# KIT_STM32F4.net
KiCad netlist of a schematic drawn in Altium Designer
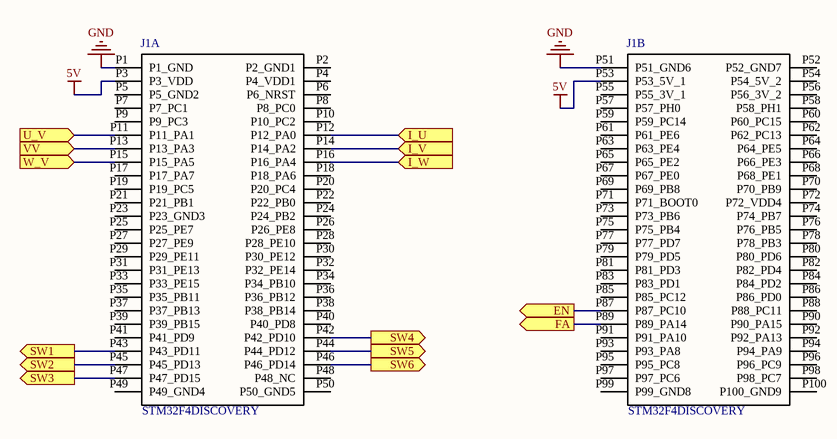
[diagram p0: KIT_STM32F4.SchDoc]

(export (version "E")
  (design (tool "Eeschema 10.0.6"))
  (components
    (comp (ref "J1")
      (value "STM32F4DISCOVERY")
      (footprint "STMICROELECTRONICS_STM32F4DISCOVERY_STM32F4DISCOVERY(Primary)")
      (description "Development kit: ARM ST; pin strips, pin header; No.of")
      (fields (field (name "MF") "STMicroelectronics"))
      (libsource (lib "SemacSYS") (part "STM32F4DISCOVERY"))
    )
  )
  (nets
    (net (code "1") (name "/EN") (class "Default")
      (node (ref "J1") (pin "P87") (pinfunction "P87_PC10_P87") (pintype "passive"))
    )
    (net (code "2") (name "/FA") (class "Default")
      (node (ref "J1") (pin "P89") (pinfunction "P89_PA14_P89") (pintype "passive"))
    )
    (net (code "3") (name "/I_U") (class "Default")
      (node (ref "J1") (pin "P12") (pinfunction "P12_PA0_P12") (pintype "passive"))
    )
    (net (code "4") (name "/I_V") (class "Default")
      (node (ref "J1") (pin "P14") (pinfunction "P14_PA2_P14") (pintype "passive"))
    )
    (net (code "5") (name "/I_W") (class "Default")
      (node (ref "J1") (pin "P16") (pinfunction "P16_PA4_P16") (pintype "passive"))
    )
    (net (code "6") (name "/SW1") (class "Default")
      (node (ref "J1") (pin "P43") (pinfunction "P43_PD11_P43") (pintype "passive"))
    )
    (net (code "7") (name "/SW2") (class "Default")
      (node (ref "J1") (pin "P45") (pinfunction "P45_PD13_P45") (pintype "passive"))
    )
    (net (code "8") (name "/SW3") (class "Default")
      (node (ref "J1") (pin "P47") (pinfunction "P47_PD15_P47") (pintype "passive"))
    )
    (net (code "9") (name "/SW4") (class "Default")
      (node (ref "J1") (pin "P42") (pinfunction "P42_PD10_P42") (pintype "passive"))
    )
    (net (code "10") (name "/SW5") (class "Default")
      (node (ref "J1") (pin "P44") (pinfunction "P44_PD12_P44") (pintype "passive"))
    )
    (net (code "11") (name "/SW6") (class "Default")
      (node (ref "J1") (pin "P46") (pinfunction "P46_PD14_P46") (pintype "passive"))
    )
    (net (code "12") (name "/U_V") (class "Default")
      (node (ref "J1") (pin "P11") (pinfunction "P11_PA1_P11") (pintype "passive"))
    )
    (net (code "13") (name "/VV") (class "Default")
      (node (ref "J1") (pin "P13") (pinfunction "P13_PA3_P13") (pintype "passive"))
    )
    (net (code "14") (name "/W_V") (class "Default")
      (node (ref "J1") (pin "P15") (pinfunction "P15_PA5_P15") (pintype "passive"))
    )
    (net (code "15") (name "5V") (class "Default")
      (node (ref "J1") (pin "P3") (pinfunction "P3_VDD_P3") (pintype "passive"))
      (node (ref "J1") (pin "P53") (pinfunction "P53_5V_1_P53") (pintype "passive"))
    )
    (net (code "16") (name "GND") (class "Default")
      (node (ref "J1") (pin "P1") (pinfunction "P1_GND_P1") (pintype "passive"))
      (node (ref "J1") (pin "P51") (pinfunction "P51_GND6_P51") (pintype "passive"))
    )
    (net (code "17") (name "unconnected-(J1A-P2_GND1-PadP2)") (class "Default")
      (node (ref "J1") (pin "P2") (pinfunction "P2_GND1_P2") (pintype "passive"))
    )
    (net (code "18") (name "unconnected-(J1A-P4_VDD1-PadP4)") (class "Default")
      (node (ref "J1") (pin "P4") (pinfunction "P4_VDD1_P4") (pintype "passive"))
    )
    (net (code "19") (name "unconnected-(J1A-P5_GND2-PadP5)") (class "Default")
      (node (ref "J1") (pin "P5") (pinfunction "P5_GND2_P5") (pintype "passive"))
    )
    (net (code "20") (name "unconnected-(J1A-P6_NRST-PadP6)") (class "Default")
      (node (ref "J1") (pin "P6") (pinfunction "P6_NRST_P6") (pintype "passive"))
    )
    (net (code "21") (name "unconnected-(J1A-P7_PC1-PadP7)") (class "Default")
      (node (ref "J1") (pin "P7") (pinfunction "P7_PC1_P7") (pintype "passive"))
    )
    (net (code "22") (name "unconnected-(J1A-P8_PC0-PadP8)") (class "Default")
      (node (ref "J1") (pin "P8") (pinfunction "P8_PC0_P8") (pintype "passive"))
    )
    (net (code "23") (name "unconnected-(J1A-P9_PC3-PadP9)") (class "Default")
      (node (ref "J1") (pin "P9") (pinfunction "P9_PC3_P9") (pintype "passive"))
    )
    (net (code "24") (name "unconnected-(J1A-P10_PC2-PadP10)") (class "Default")
      (node (ref "J1") (pin "P10") (pinfunction "P10_PC2_P10") (pintype "passive"))
    )
    (net (code "25") (name "unconnected-(J1A-P17_PA7-PadP17)") (class "Default")
      (node (ref "J1") (pin "P17") (pinfunction "P17_PA7_P17") (pintype "passive"))
    )
    (net (code "26") (name "unconnected-(J1A-P18_PA6-PadP18)") (class "Default")
      (node (ref "J1") (pin "P18") (pinfunction "P18_PA6_P18") (pintype "passive"))
    )
    (net (code "27") (name "unconnected-(J1A-P19_PC5-PadP19)") (class "Default")
      (node (ref "J1") (pin "P19") (pinfunction "P19_PC5_P19") (pintype "passive"))
    )
    (net (code "28") (name "unconnected-(J1A-P20_PC4-PadP20)") (class "Default")
      (node (ref "J1") (pin "P20") (pinfunction "P20_PC4_P20") (pintype "passive"))
    )
    (net (code "29") (name "unconnected-(J1A-P21_PB1-PadP21)") (class "Default")
      (node (ref "J1") (pin "P21") (pinfunction "P21_PB1_P21") (pintype "passive"))
    )
    (net (code "30") (name "unconnected-(J1A-P22_PB0-PadP22)") (class "Default")
      (node (ref "J1") (pin "P22") (pinfunction "P22_PB0_P22") (pintype "passive"))
    )
    (net (code "31") (name "unconnected-(J1A-P23_GND3-PadP23)") (class "Default")
      (node (ref "J1") (pin "P23") (pinfunction "P23_GND3_P23") (pintype "passive"))
    )
    (net (code "32") (name "unconnected-(J1A-P24_PB2-PadP24)") (class "Default")
      (node (ref "J1") (pin "P24") (pinfunction "P24_PB2_P24") (pintype "passive"))
    )
    (net (code "33") (name "unconnected-(J1A-P25_PE7-PadP25)") (class "Default")
      (node (ref "J1") (pin "P25") (pinfunction "P25_PE7_P25") (pintype "passive"))
    )
    (net (code "34") (name "unconnected-(J1A-P26_PE8-PadP26)") (class "Default")
      (node (ref "J1") (pin "P26") (pinfunction "P26_PE8_P26") (pintype "passive"))
    )
    (net (code "35") (name "unconnected-(J1A-P27_PE9-PadP27)") (class "Default")
      (node (ref "J1") (pin "P27") (pinfunction "P27_PE9_P27") (pintype "passive"))
    )
    (net (code "36") (name "unconnected-(J1A-P28_PE10-PadP28)") (class "Default")
      (node (ref "J1") (pin "P28") (pinfunction "P28_PE10_P28") (pintype "passive"))
    )
    (net (code "37") (name "unconnected-(J1A-P29_PE11-PadP29)") (class "Default")
      (node (ref "J1") (pin "P29") (pinfunction "P29_PE11_P29") (pintype "passive"))
    )
    (net (code "38") (name "unconnected-(J1A-P30_PE12-PadP30)") (class "Default")
      (node (ref "J1") (pin "P30") (pinfunction "P30_PE12_P30") (pintype "passive"))
    )
    (net (code "39") (name "unconnected-(J1A-P31_PE13-PadP31)") (class "Default")
      (node (ref "J1") (pin "P31") (pinfunction "P31_PE13_P31") (pintype "passive"))
    )
    (net (code "40") (name "unconnected-(J1A-P32_PE14-PadP32)") (class "Default")
      (node (ref "J1") (pin "P32") (pinfunction "P32_PE14_P32") (pintype "passive"))
    )
    (net (code "41") (name "unconnected-(J1A-P33_PE15-PadP33)") (class "Default")
      (node (ref "J1") (pin "P33") (pinfunction "P33_PE15_P33") (pintype "passive"))
    )
    (net (code "42") (name "unconnected-(J1A-P34_PB10-PadP34)") (class "Default")
      (node (ref "J1") (pin "P34") (pinfunction "P34_PB10_P34") (pintype "passive"))
    )
    (net (code "43") (name "unconnected-(J1A-P35_PB11-PadP35)") (class "Default")
      (node (ref "J1") (pin "P35") (pinfunction "P35_PB11_P35") (pintype "passive"))
    )
    (net (code "44") (name "unconnected-(J1A-P36_PB12-PadP36)") (class "Default")
      (node (ref "J1") (pin "P36") (pinfunction "P36_PB12_P36") (pintype "passive"))
    )
    (net (code "45") (name "unconnected-(J1A-P37_PB13-PadP37)") (class "Default")
      (node (ref "J1") (pin "P37") (pinfunction "P37_PB13_P37") (pintype "passive"))
    )
    (net (code "46") (name "unconnected-(J1A-P38_PB14-PadP38)") (class "Default")
      (node (ref "J1") (pin "P38") (pinfunction "P38_PB14_P38") (pintype "passive"))
    )
    (net (code "47") (name "unconnected-(J1A-P39_PB15-PadP39)") (class "Default")
      (node (ref "J1") (pin "P39") (pinfunction "P39_PB15_P39") (pintype "passive"))
    )
    (net (code "48") (name "unconnected-(J1A-P40_PD8-PadP40)") (class "Default")
      (node (ref "J1") (pin "P40") (pinfunction "P40_PD8_P40") (pintype "passive"))
    )
    (net (code "49") (name "unconnected-(J1A-P41_PD9-PadP41)") (class "Default")
      (node (ref "J1") (pin "P41") (pinfunction "P41_PD9_P41") (pintype "passive"))
    )
    (net (code "50") (name "unconnected-(J1A-P48_NC-PadP48)") (class "Default")
      (node (ref "J1") (pin "P48") (pinfunction "P48_NC_P48") (pintype "passive"))
    )
    (net (code "51") (name "unconnected-(J1A-P49_GND4-PadP49)") (class "Default")
      (node (ref "J1") (pin "P49") (pinfunction "P49_GND4_P49") (pintype "passive"))
    )
    (net (code "52") (name "unconnected-(J1A-P50_GND5-PadP50)") (class "Default")
      (node (ref "J1") (pin "P50") (pinfunction "P50_GND5_P50") (pintype "passive"))
    )
    (net (code "53") (name "unconnected-(J1B-P52_GND7-PadP52)") (class "Default")
      (node (ref "J1") (pin "P52") (pinfunction "P52_GND7_P52") (pintype "passive"))
    )
    (net (code "54") (name "unconnected-(J1B-P54_5V_2-PadP54)") (class "Default")
      (node (ref "J1") (pin "P54") (pinfunction "P54_5V_2_P54") (pintype "passive"))
    )
    (net (code "55") (name "unconnected-(J1B-P55_3V_1-PadP55)") (class "Default")
      (node (ref "J1") (pin "P55") (pinfunction "P55_3V_1_P55") (pintype "passive"))
    )
    (net (code "56") (name "unconnected-(J1B-P56_3V_2-PadP56)") (class "Default")
      (node (ref "J1") (pin "P56") (pinfunction "P56_3V_2_P56") (pintype "passive"))
    )
    (net (code "57") (name "unconnected-(J1B-P57_PH0-PadP57)") (class "Default")
      (node (ref "J1") (pin "P57") (pinfunction "P57_PH0_P57") (pintype "passive"))
    )
    (net (code "58") (name "unconnected-(J1B-P58_PH1-PadP58)") (class "Default")
      (node (ref "J1") (pin "P58") (pinfunction "P58_PH1_P58") (pintype "passive"))
    )
    (net (code "59") (name "unconnected-(J1B-P59_PC14-PadP59)") (class "Default")
      (node (ref "J1") (pin "P59") (pinfunction "P59_PC14_P59") (pintype "passive"))
    )
    (net (code "60") (name "unconnected-(J1B-P60_PC15-PadP60)") (class "Default")
      (node (ref "J1") (pin "P60") (pinfunction "P60_PC15_P60") (pintype "passive"))
    )
    (net (code "61") (name "unconnected-(J1B-P61_PE6-PadP61)") (class "Default")
      (node (ref "J1") (pin "P61") (pinfunction "P61_PE6_P61") (pintype "passive"))
    )
    (net (code "62") (name "unconnected-(J1B-P62_PC13-PadP62)") (class "Default")
      (node (ref "J1") (pin "P62") (pinfunction "P62_PC13_P62") (pintype "passive"))
    )
    (net (code "63") (name "unconnected-(J1B-P63_PE4-PadP63)") (class "Default")
      (node (ref "J1") (pin "P63") (pinfunction "P63_PE4_P63") (pintype "passive"))
    )
    (net (code "64") (name "unconnected-(J1B-P64_PE5-PadP64)") (class "Default")
      (node (ref "J1") (pin "P64") (pinfunction "P64_PE5_P64") (pintype "passive"))
    )
    (net (code "65") (name "unconnected-(J1B-P65_PE2-PadP65)") (class "Default")
      (node (ref "J1") (pin "P65") (pinfunction "P65_PE2_P65") (pintype "passive"))
    )
    (net (code "66") (name "unconnected-(J1B-P66_PE3-PadP66)") (class "Default")
      (node (ref "J1") (pin "P66") (pinfunction "P66_PE3_P66") (pintype "passive"))
    )
    (net (code "67") (name "unconnected-(J1B-P67_PE0-PadP67)") (class "Default")
      (node (ref "J1") (pin "P67") (pinfunction "P67_PE0_P67") (pintype "passive"))
    )
    (net (code "68") (name "unconnected-(J1B-P68_PE1-PadP68)") (class "Default")
      (node (ref "J1") (pin "P68") (pinfunction "P68_PE1_P68") (pintype "passive"))
    )
    (net (code "69") (name "unconnected-(J1B-P69_PB8-PadP69)") (class "Default")
      (node (ref "J1") (pin "P69") (pinfunction "P69_PB8_P69") (pintype "passive"))
    )
    (net (code "70") (name "unconnected-(J1B-P70_PB9-PadP70)") (class "Default")
      (node (ref "J1") (pin "P70") (pinfunction "P70_PB9_P70") (pintype "passive"))
    )
    (net (code "71") (name "unconnected-(J1B-P71_BOOT0-PadP71)") (class "Default")
      (node (ref "J1") (pin "P71") (pinfunction "P71_BOOT0_P71") (pintype "passive"))
    )
    (net (code "72") (name "unconnected-(J1B-P72_VDD4-PadP72)") (class "Default")
      (node (ref "J1") (pin "P72") (pinfunction "P72_VDD4_P72") (pintype "passive"))
    )
    (net (code "73") (name "unconnected-(J1B-P73_PB6-PadP73)") (class "Default")
      (node (ref "J1") (pin "P73") (pinfunction "P73_PB6_P73") (pintype "passive"))
    )
    (net (code "74") (name "unconnected-(J1B-P74_PB7-PadP74)") (class "Default")
      (node (ref "J1") (pin "P74") (pinfunction "P74_PB7_P74") (pintype "passive"))
    )
    (net (code "75") (name "unconnected-(J1B-P75_PB4-PadP75)") (class "Default")
      (node (ref "J1") (pin "P75") (pinfunction "P75_PB4_P75") (pintype "passive"))
    )
    (net (code "76") (name "unconnected-(J1B-P76_PB5-PadP76)") (class "Default")
      (node (ref "J1") (pin "P76") (pinfunction "P76_PB5_P76") (pintype "passive"))
    )
    (net (code "77") (name "unconnected-(J1B-P77_PD7-PadP77)") (class "Default")
      (node (ref "J1") (pin "P77") (pinfunction "P77_PD7_P77") (pintype "passive"))
    )
    (net (code "78") (name "unconnected-(J1B-P78_PB3-PadP78)") (class "Default")
      (node (ref "J1") (pin "P78") (pinfunction "P78_PB3_P78") (pintype "passive"))
    )
    (net (code "79") (name "unconnected-(J1B-P79_PD5-PadP79)") (class "Default")
      (node (ref "J1") (pin "P79") (pinfunction "P79_PD5_P79") (pintype "passive"))
    )
    (net (code "80") (name "unconnected-(J1B-P80_PD6-PadP80)") (class "Default")
      (node (ref "J1") (pin "P80") (pinfunction "P80_PD6_P80") (pintype "passive"))
    )
    (net (code "81") (name "unconnected-(J1B-P81_PD3-PadP81)") (class "Default")
      (node (ref "J1") (pin "P81") (pinfunction "P81_PD3_P81") (pintype "passive"))
    )
    (net (code "82") (name "unconnected-(J1B-P82_PD4-PadP82)") (class "Default")
      (node (ref "J1") (pin "P82") (pinfunction "P82_PD4_P82") (pintype "passive"))
    )
    (net (code "83") (name "unconnected-(J1B-P83_PD1-PadP83)") (class "Default")
      (node (ref "J1") (pin "P83") (pinfunction "P83_PD1_P83") (pintype "passive"))
    )
    (net (code "84") (name "unconnected-(J1B-P84_PD2-PadP84)") (class "Default")
      (node (ref "J1") (pin "P84") (pinfunction "P84_PD2_P84") (pintype "passive"))
    )
    (net (code "85") (name "unconnected-(J1B-P85_PC12-PadP85)") (class "Default")
      (node (ref "J1") (pin "P85") (pinfunction "P85_PC12_P85") (pintype "passive"))
    )
    (net (code "86") (name "unconnected-(J1B-P86_PD0-PadP86)") (class "Default")
      (node (ref "J1") (pin "P86") (pinfunction "P86_PD0_P86") (pintype "passive"))
    )
    (net (code "87") (name "unconnected-(J1B-P88_PC11-PadP88)") (class "Default")
      (node (ref "J1") (pin "P88") (pinfunction "P88_PC11_P88") (pintype "passive"))
    )
    (net (code "88") (name "unconnected-(J1B-P90_PA15-PadP90)") (class "Default")
      (node (ref "J1") (pin "P90") (pinfunction "P90_PA15_P90") (pintype "passive"))
    )
    (net (code "89") (name "unconnected-(J1B-P91_PA10-PadP91)") (class "Default")
      (node (ref "J1") (pin "P91") (pinfunction "P91_PA10_P91") (pintype "passive"))
    )
    (net (code "90") (name "unconnected-(J1B-P92_PA13-PadP92)") (class "Default")
      (node (ref "J1") (pin "P92") (pinfunction "P92_PA13_P92") (pintype "passive"))
    )
    (net (code "91") (name "unconnected-(J1B-P93_PA8-PadP93)") (class "Default")
      (node (ref "J1") (pin "P93") (pinfunction "P93_PA8_P93") (pintype "passive"))
    )
    (net (code "92") (name "unconnected-(J1B-P94_PA9-PadP94)") (class "Default")
      (node (ref "J1") (pin "P94") (pinfunction "P94_PA9_P94") (pintype "passive"))
    )
    (net (code "93") (name "unconnected-(J1B-P95_PC8-PadP95)") (class "Default")
      (node (ref "J1") (pin "P95") (pinfunction "P95_PC8_P95") (pintype "passive"))
    )
    (net (code "94") (name "unconnected-(J1B-P96_PC9-PadP96)") (class "Default")
      (node (ref "J1") (pin "P96") (pinfunction "P96_PC9_P96") (pintype "passive"))
    )
    (net (code "95") (name "unconnected-(J1B-P97_PC6-PadP97)") (class "Default")
      (node (ref "J1") (pin "P97") (pinfunction "P97_PC6_P97") (pintype "passive"))
    )
    (net (code "96") (name "unconnected-(J1B-P98_PC7-PadP98)") (class "Default")
      (node (ref "J1") (pin "P98") (pinfunction "P98_PC7_P98") (pintype "passive"))
    )
    (net (code "97") (name "unconnected-(J1B-P99_GND8-PadP99)") (class "Default")
      (node (ref "J1") (pin "P99") (pinfunction "P99_GND8_P99") (pintype "passive"))
    )
    (net (code "98") (name "unconnected-(J1B-P100_GND9-PadP100)") (class "Default")
      (node (ref "J1") (pin "P100") (pinfunction "P100_GND9_P100") (pintype "passive"))
    )
  )
)
